# Top_Level.net
KiCad netlist of a schematic drawn in Altium Designer
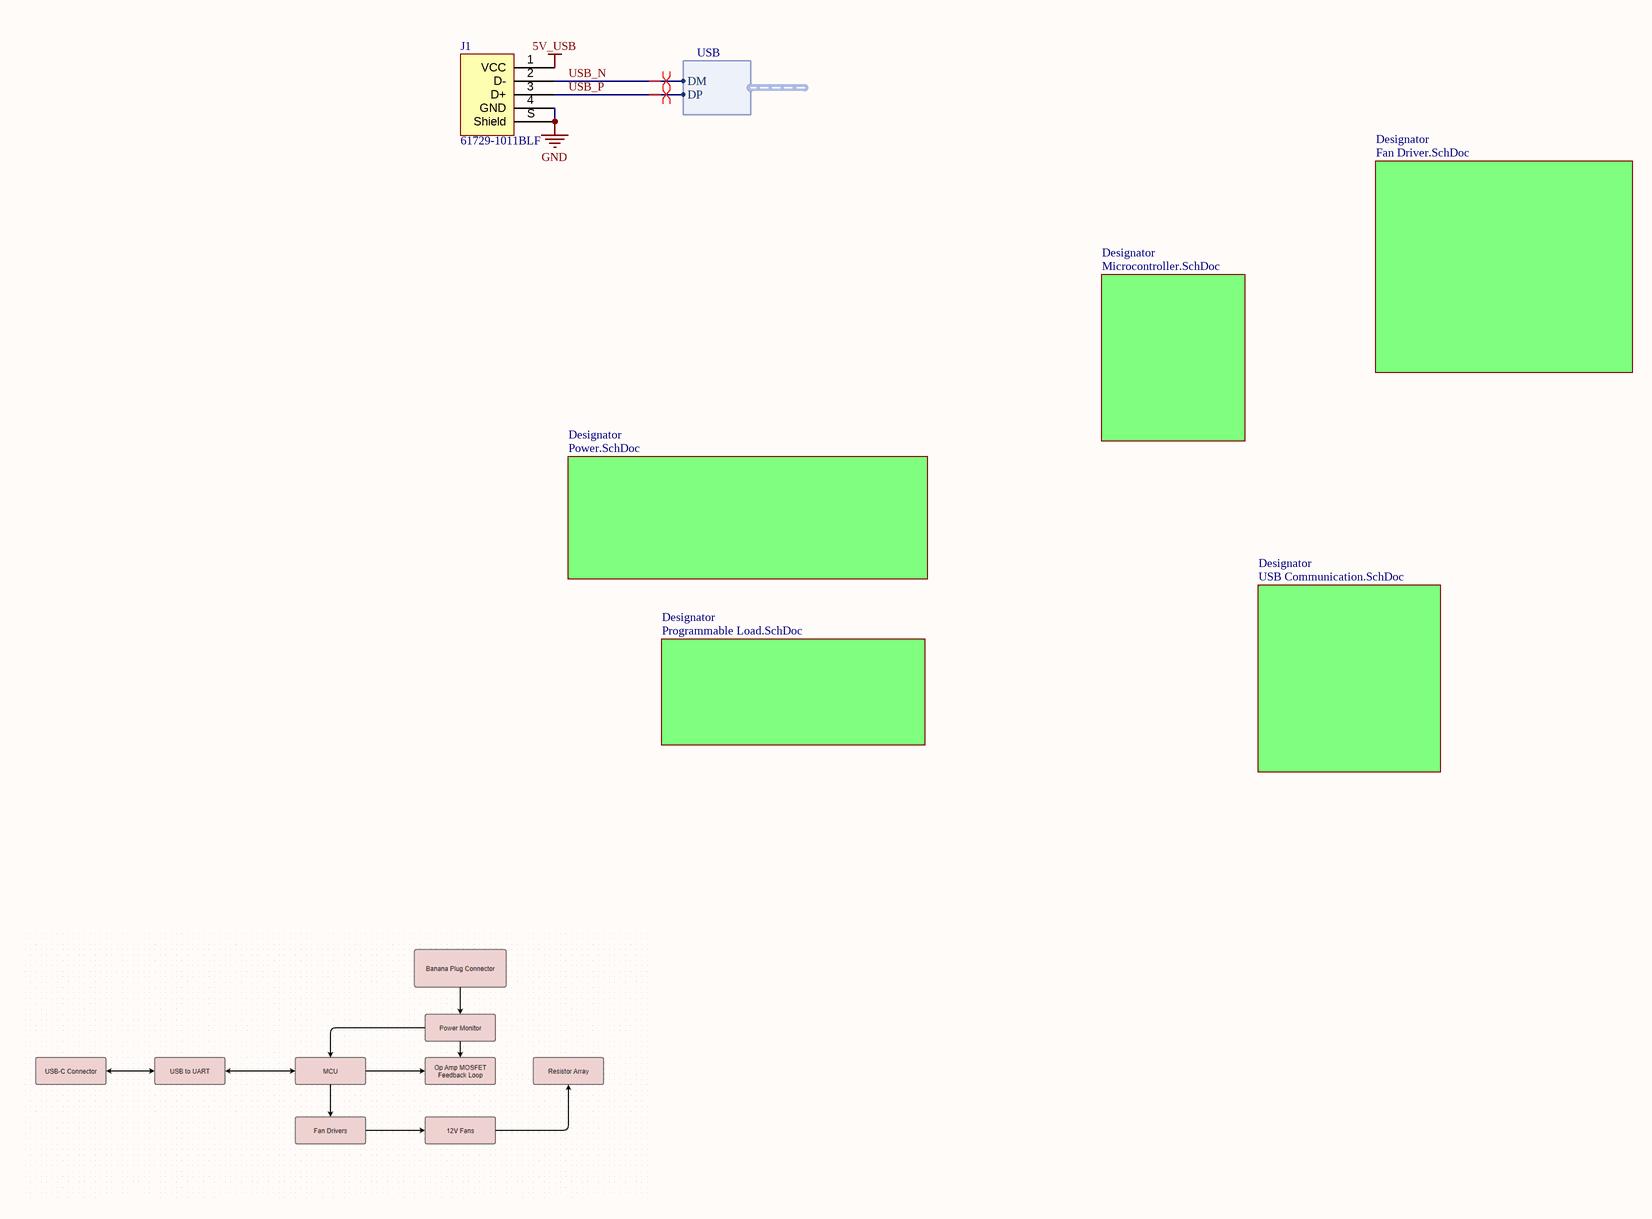
[diagram p0: Top Level.SchDoc]

(export (version "E")
  (design (tool "Eeschema 10.0.6"))
  (components
    (comp (ref "J1")
      (value "61729-1011BLF")
      (footprint "FCI USB 61729-1011BLF")
      (description "CONN RCPT USB2.0 TYPEB 4POS R/A")
      (fields (field (name "MANUFACTURER") "Amphenol ICC (FCI)"))
      (libsource (lib "Celestial Altium Library - altium_library") (part "USB 2.0 Type B"))
    )
  )
  (nets
    (net (code "2") (name "/USB_N") (class "Default")
      (node (ref "J1") (pin "2") (pinfunction "D-_2") (pintype "passive"))
    )
    (net (code "3") (name "/USB_P") (class "Default")
      (node (ref "J1") (pin "3") (pinfunction "D+_3") (pintype "passive"))
    )
    (net (code "5") (name "5V_USB") (class "Default")
      (node (ref "J1") (pin "1") (pinfunction "VCC_1") (pintype "passive"))
    )
    (net (code "6") (name "GND") (class "Default")
      (node (ref "J1") (pin "4") (pinfunction "GND_4") (pintype "passive"))
      (node (ref "J1") (pin "S") (pinfunction "Shield_S") (pintype "passive"))
    )
  )
)
